# MCU.net
KiCad netlist of a schematic drawn in Altium Designer
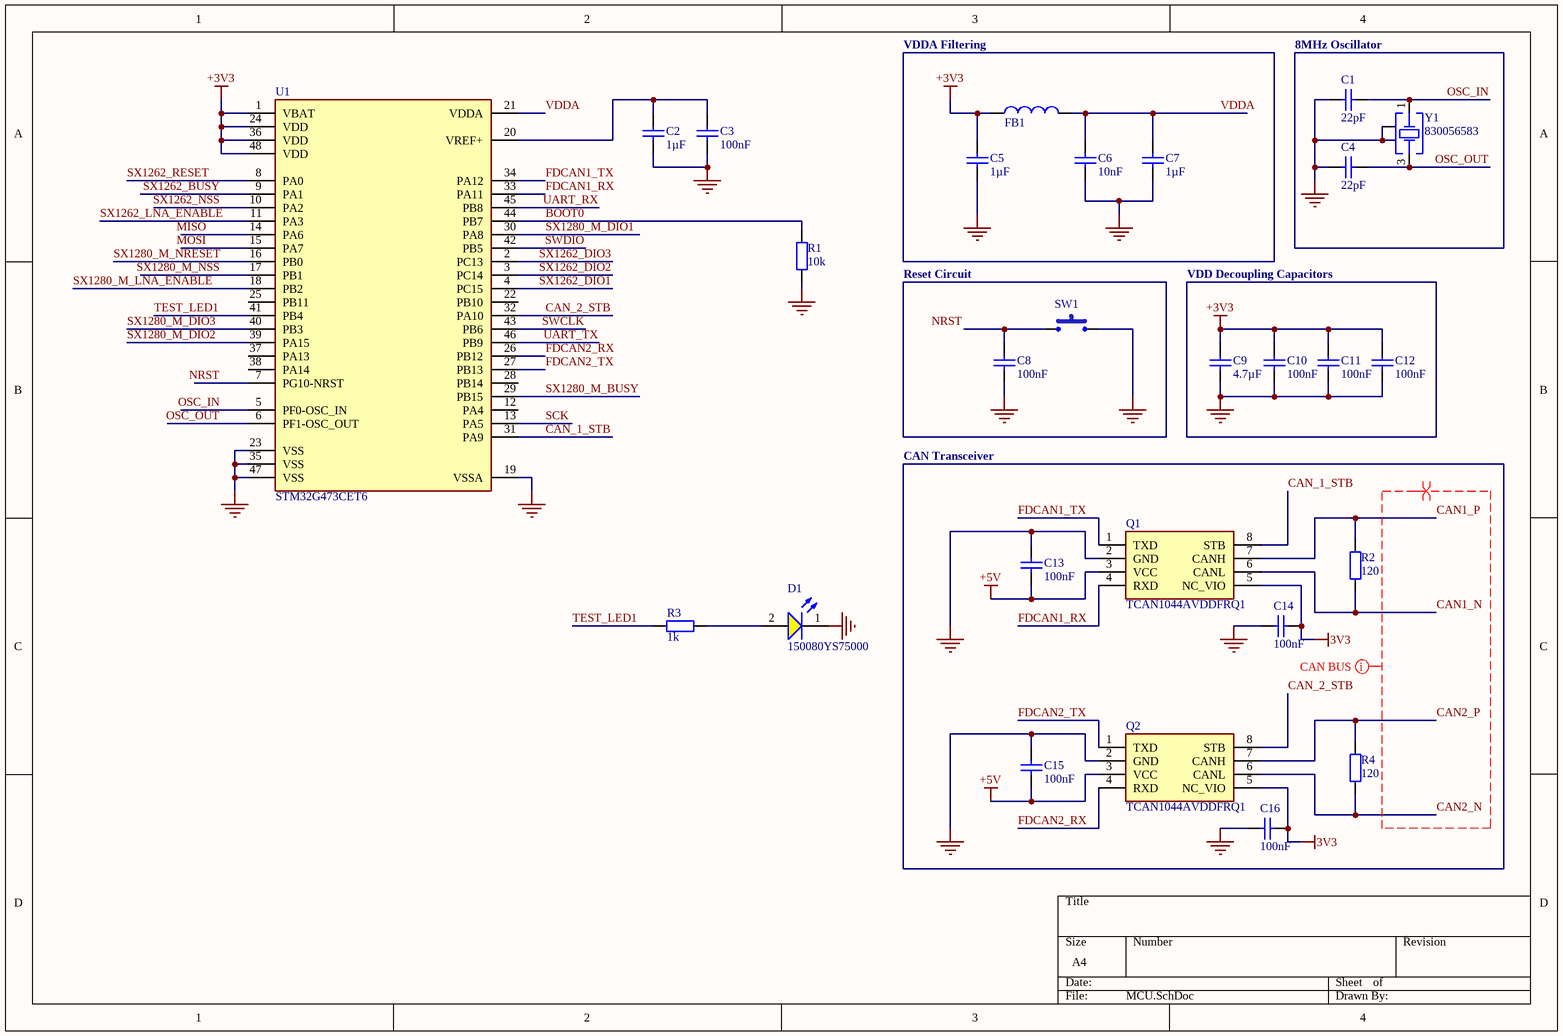
[diagram p0: MCU.SchDoc]

(export (version "E")
  (design (tool "Eeschema 10.0.6"))
  (components
    (comp (ref "C1")
      (value "22pF")
      (footprint "WCAP-CSGP_0603_L1.6W0.8H0.8_Reflow")
      (description "WCAP-CSGP Multilayer Ceramic Chip Capacitor, General Purpose, size 0603, NP0, 22pF, 25VDC")
      (fields
        (field (name "MANUFACTURER") "Wurth Elektronik")
        (field (name "MANUFACTURER PART NUMBER") "885012006034")
      )
      (libsource (lib "LEEM UPM") (part "885012209047R"))
    )
    (comp (ref "C2")
      (value "1µF")
      (footprint "WCAP-CSGP_0603_L1.6W0.8H0.8_Reflow")
      (description "WCAP-CSGP Multilayer Ceramic Chip Capacitor, General Purpose, size 0603, X7R, 1uF, 16VDC")
      (fields
        (field (name "MANUFACTURER") "Wurth Elektronik")
        (field (name "MANUFACTURER PART NUMBER") "885012206052")
      )
      (libsource (lib "LEEM UPM") (part "885012209047R"))
    )
    (comp (ref "C3")
      (value "100nF")
      (footprint "WCAP-CSGP_0603_L1.6W0.8H0.8_Reflow")
      (description "WCAP-CSGP Multilayer Ceramic Chip Capacitor, General Purpose, size 0603, X7R, 100nF, 25VDC")
      (fields
        (field (name "MANUFACTURER") "Wurth Elektronik")
        (field (name "MANUFACTURER PART NUMBER") "885012206071")
      )
      (libsource (lib "LEEM UPM") (part "885012209047R"))
    )
    (comp (ref "C4")
      (value "22pF")
      (footprint "WCAP-CSGP_0603_L1.6W0.8H0.8_Reflow")
      (description "WCAP-CSGP Multilayer Ceramic Chip Capacitor, General Purpose, size 0603, NP0, 22pF, 25VDC")
      (fields
        (field (name "MANUFACTURER") "Wurth Elektronik")
        (field (name "MANUFACTURER PART NUMBER") "885012006034")
      )
      (libsource (lib "LEEM UPM") (part "885012209047R"))
    )
    (comp (ref "C5")
      (value "1µF")
      (footprint "WCAP-CSGP_0603_L1.6W0.8H0.8_Reflow")
      (description "WCAP-CSGP Multilayer Ceramic Chip Capacitor, General Purpose, size 0603, X7R, 1uF, 16VDC")
      (fields
        (field (name "MANUFACTURER") "Wurth Elektronik")
        (field (name "MANUFACTURER PART NUMBER") "885012206052")
      )
      (libsource (lib "LEEM UPM") (part "885012209047R"))
    )
    (comp (ref "C6")
      (value "10nF")
      (footprint "WCAP-CSGP_0603_L1.6W0.8H0.8_Reflow")
      (description "WCAP-CSGP Multilayer Ceramic Chip Capacitor, General Purpose, size 0603, X7R, 10nF, 25VDC")
      (fields
        (field (name "MANUFACTURER") "Wurth Elektronik")
        (field (name "MANUFACTURER PART NUMBER") "885012206065")
      )
      (libsource (lib "LEEM UPM") (part "885012209047R"))
    )
    (comp (ref "C7")
      (value "1µF")
      (footprint "WCAP-CSGP_0603_L1.6W0.8H0.8_Reflow")
      (description "WCAP-CSGP Multilayer Ceramic Chip Capacitor, General Purpose, size 0603, X7R, 1uF, 16VDC")
      (fields
        (field (name "MANUFACTURER") "Wurth Elektronik")
        (field (name "MANUFACTURER PART NUMBER") "885012206052")
      )
      (libsource (lib "LEEM UPM") (part "885012209047R"))
    )
    (comp (ref "C8")
      (value "100nF")
      (footprint "WCAP-CSGP_0603_L1.6W0.8H0.8_Reflow")
      (description "WCAP-CSGP Multilayer Ceramic Chip Capacitor, General Purpose, size 0603, X7R, 100nF, 25VDC")
      (fields
        (field (name "MANUFACTURER") "Wurth Elektronik")
        (field (name "MANUFACTURER PART NUMBER") "885012206071")
      )
      (libsource (lib "LEEM UPM") (part "885012209047R"))
    )
    (comp (ref "C9")
      (value "4.7µF")
      (footprint "WCAP-CSGP_0603_L1.6W0.8H0.8_Reflow")
      (description "WCAP-CSGP Multilayer Ceramic Chip Capacitor, General Purpose, size 0603, X5R, 4.7uF, 10VDC")
      (fields
        (field (name "MANUFACTURER PART NUMBER") "885012106012")
        (field (name "MANUFACTURER") "Wurth Elektronik")
      )
      (libsource (lib "LEEM UPM") (part "885012209047R"))
    )
    (comp (ref "C10")
      (value "100nF")
      (footprint "WCAP-CSGP_0603_L1.6W0.8H0.8_Reflow")
      (description "WCAP-CSGP Multilayer Ceramic Chip Capacitor, General Purpose, size 0603, X7R, 100nF, 25VDC")
      (fields
        (field (name "MANUFACTURER") "Wurth Elektronik")
        (field (name "MANUFACTURER PART NUMBER") "885012206071")
      )
      (libsource (lib "LEEM UPM") (part "885012209047R"))
    )
    (comp (ref "C11")
      (value "100nF")
      (footprint "WCAP-CSGP_0603_L1.6W0.8H0.8_Reflow")
      (description "WCAP-CSGP Multilayer Ceramic Chip Capacitor, General Purpose, size 0603, X7R, 100nF, 25VDC")
      (fields
        (field (name "MANUFACTURER") "Wurth Elektronik")
        (field (name "MANUFACTURER PART NUMBER") "885012206071")
      )
      (libsource (lib "LEEM UPM") (part "885012209047R"))
    )
    (comp (ref "C12")
      (value "100nF")
      (footprint "WCAP-CSGP_0603_L1.6W0.8H0.8_Reflow")
      (description "WCAP-CSGP Multilayer Ceramic Chip Capacitor, General Purpose, size 0603, X7R, 100nF, 25VDC")
      (fields
        (field (name "MANUFACTURER") "Wurth Elektronik")
        (field (name "MANUFACTURER PART NUMBER") "885012206071")
      )
      (libsource (lib "LEEM UPM") (part "885012209047R"))
    )
    (comp (ref "C13")
      (value "100nF")
      (footprint "WCAP-CSGP_0603_L1.6W0.8H0.8_Reflow")
      (description "WCAP-CSGP Multilayer Ceramic Chip Capacitor, General Purpose, size 0603, X7R, 100nF, 25VDC")
      (fields
        (field (name "MANUFACTURER") "Wurth Elektronik")
        (field (name "MANUFACTURER PART NUMBER") "885012206071")
      )
      (libsource (lib "LEEM UPM") (part "885012209047R"))
    )
    (comp (ref "C14")
      (value "100nF")
      (footprint "WCAP-CSGP_0603_L1.6W0.8H0.8_Reflow")
      (description "WCAP-CSGP Multilayer Ceramic Chip Capacitor, General Purpose, size 0603, X7R, 100nF, 25VDC")
      (fields
        (field (name "MANUFACTURER") "Wurth Elektronik")
        (field (name "MANUFACTURER PART NUMBER") "885012206071")
      )
      (libsource (lib "LEEM UPM") (part "885012209047R"))
    )
    (comp (ref "C15")
      (value "100nF")
      (footprint "WCAP-CSGP_0603_L1.6W0.8H0.8_Reflow")
      (description "WCAP-CSGP Multilayer Ceramic Chip Capacitor, General Purpose, size 0603, X7R, 100nF, 25VDC")
      (fields
        (field (name "MANUFACTURER") "Wurth Elektronik")
        (field (name "MANUFACTURER PART NUMBER") "885012206071")
      )
      (libsource (lib "LEEM UPM") (part "885012209047R"))
    )
    (comp (ref "C16")
      (value "100nF")
      (footprint "WCAP-CSGP_0603_L1.6W0.8H0.8_Reflow")
      (description "WCAP-CSGP Multilayer Ceramic Chip Capacitor, General Purpose, size 0603, X7R, 100nF, 25VDC")
      (fields
        (field (name "MANUFACTURER") "Wurth Elektronik")
        (field (name "MANUFACTURER PART NUMBER") "885012206071")
      )
      (libsource (lib "LEEM UPM") (part "885012209047R"))
    )
    (comp (ref "D1")
      (value "150080YS75000")
      (footprint "WL-SMCW_0805_150080xx75000")
      (description "WL-SMCW Mono-color Chip LED Waterclear, SMT, size 0805, Yellow, 2V, 140°")
      (fields (field (name "MANUFACTURER") "Wurth Elektronik"))
      (libsource (lib "LEEM UPM") (part "150120YS87000"))
    )
    (comp (ref "FB1")
      (value "742792625")
      (footprint "WE-CBF_0603_L1.6W0.8H0.8_HC")
      (description "WE-CBF SMT EMI Suppression Ferrite Bead, size 0603, 120Ohm, 2A")
      (fields (field (name "MANUFACTURER") "Wurth Elektronik"))
      (libsource (lib "LEEM UPM") (part "7427928801"))
    )
    (comp (ref "Q1")
      (value "TCAN1044AVDDFRQ1")
      (footprint "FP-DDF0008A-MFG")
      (description "Enhanced automotive CAN transceiver with standby 8-SOT-23-THIN -40 to 150")
      (libsource (lib "LEEM UPM") (part "TCAN1044A"))
    )
    (comp (ref "Q2")
      (value "TCAN1044AVDDFRQ1")
      (footprint "FP-DDF0008A-MFG")
      (description "Enhanced automotive CAN transceiver with standby 8-SOT-23-THIN -40 to 150")
      (libsource (lib "LEEM UPM") (part "TCAN1044A"))
    )
    (comp (ref "R1")
      (value "10k")
      (footprint "WRIS-RSKS_0603_Reflow")
      (description "WRIS-RSKS Thick Film Resistor, size 0603, 10000Ohm, 100mW")
      (fields
        (field (name "MANUFACTURER") "Wurth Elektronik")
        (field (name "MANUFACTURER PART NUMBER") "560112116005")
      )
      (libsource (lib "") (part "560112140010_1"))
    )
    (comp (ref "R2")
      (value "120")
      (footprint "RCS0805120RFKEA-Footprint-1")
      (fields (field (name "POWER") "500mW") (field (name "Comment") "RCS0805120RFKEA"))
      (libsource (lib "LEEM UPM") (part "RCS0805120"))
    )
    (comp (ref "R3")
      (value "1k")
      (footprint "WRIS-RSKS_0603_Reflow")
      (description "WRIS-RSKS Thick Film Resistor, size 0603, 1000Ohm, 100mW")
      (fields
        (field (name "MANUFACTURER PART NUMBER") "560112116014")
        (field (name "MANUFACTURER") "Wurth Elektronik")
      )
      (libsource (lib "LEEM UPM") (part "560112140010"))
    )
    (comp (ref "R4")
      (value "120")
      (footprint "RCS0805120RFKEA-Footprint-1")
      (fields (field (name "POWER") "500mW") (field (name "Comment") "RCS0805120RFKEA"))
      (libsource (lib "LEEM UPM") (part "RCS0805120"))
    )
    (comp (ref "SW1")
      (value "PTS815SJM250SMTRLFS")
      (footprint "PTS815SJM250SMTRLFS-Footprint-1")
      (libsource (lib "LEEM UPM") (part "PTS815S"))
    )
    (comp (ref "U1")
      (value "STM32G473CET6")
      (footprint "STM32G0C1RET6-Footprint-1")
      (libsource (lib "LEEM UPM") (part "STM32G473xE"))
    )
    (comp (ref "Y1")
      (value "830056583")
      (footprint "WE-XTAL_CFPX-104")
      (description "WE-XTAL Quartz Crystal, SMT, CFPX-104, 10MHz, +/-30ppm")
      (fields (field (name "MANUFACTURER") "Wurth Elektronik"))
      (libsource (lib "LEEM UPM") (part "830108161901"))
    )
  )
  (nets
    (net (code "1") (name "+3V3") (class "Default")
      (node (ref "C10") (pin "2") (pinfunction "2_2") (pintype "passive"))
      (node (ref "C11") (pin "2") (pinfunction "2_2") (pintype "passive"))
      (node (ref "C12") (pin "2") (pinfunction "2_2") (pintype "passive"))
      (node (ref "C14") (pin "1") (pinfunction "1_1") (pintype "passive"))
      (node (ref "C16") (pin "1") (pinfunction "1_1") (pintype "passive"))
      (node (ref "C5") (pin "2") (pinfunction "2_2") (pintype "passive"))
      (node (ref "C9") (pin "2") (pinfunction "2_2") (pintype "passive"))
      (node (ref "FB1") (pin "1") (pinfunction "1_1") (pintype "passive"))
      (node (ref "Q1") (pin "5") (pinfunction "NC_VIO_5") (pintype "passive"))
      (node (ref "Q2") (pin "5") (pinfunction "NC_VIO_5") (pintype "passive"))
      (node (ref "U1") (pin "1") (pinfunction "VBAT_1") (pintype "passive"))
      (node (ref "U1") (pin "24") (pinfunction "VDD_24") (pintype "passive"))
      (node (ref "U1") (pin "36") (pinfunction "VDD_36") (pintype "passive"))
      (node (ref "U1") (pin "48") (pinfunction "VDD_48") (pintype "passive"))
    )
    (net (code "2") (name "+5V") (class "Default")
      (node (ref "C13") (pin "1") (pinfunction "1_1") (pintype "passive"))
      (node (ref "C15") (pin "1") (pinfunction "1_1") (pintype "passive"))
      (node (ref "Q1") (pin "3") (pinfunction "VCC_3") (pintype "passive"))
      (node (ref "Q2") (pin "3") (pinfunction "VCC_3") (pintype "passive"))
    )
    (net (code "3") (name "/BOOT0") (class "Default")
      (node (ref "R1") (pin "2") (pinfunction "2_2") (pintype "passive"))
      (node (ref "U1") (pin "44") (pinfunction "PB7_44") (pintype "passive"))
    )
    (net (code "4") (name "/CAN1_N") (class "Default")
      (node (ref "Q1") (pin "6") (pinfunction "CANL_6") (pintype "passive"))
      (node (ref "R2") (pin "1") (pinfunction "1_1") (pintype "passive"))
    )
    (net (code "5") (name "/CAN1_P") (class "Default")
      (node (ref "Q1") (pin "7") (pinfunction "CANH_7") (pintype "passive"))
      (node (ref "R2") (pin "2") (pinfunction "2_2") (pintype "passive"))
    )
    (net (code "6") (name "/CAN2_N") (class "Default")
      (node (ref "Q2") (pin "6") (pinfunction "CANL_6") (pintype "passive"))
      (node (ref "R4") (pin "1") (pinfunction "1_1") (pintype "passive"))
    )
    (net (code "7") (name "/CAN2_P") (class "Default")
      (node (ref "Q2") (pin "7") (pinfunction "CANH_7") (pintype "passive"))
      (node (ref "R4") (pin "2") (pinfunction "2_2") (pintype "passive"))
    )
    (net (code "8") (name "/CAN_1_STB") (class "Default")
      (node (ref "Q1") (pin "8") (pinfunction "STB_8") (pintype "passive"))
      (node (ref "U1") (pin "31") (pinfunction "PA9_31") (pintype "passive"))
    )
    (net (code "9") (name "/CAN_2_STB") (class "Default")
      (node (ref "Q2") (pin "8") (pinfunction "STB_8") (pintype "passive"))
      (node (ref "U1") (pin "32") (pinfunction "PA10_32") (pintype "passive"))
    )
    (net (code "10") (name "/FDCAN1_RX") (class "Default")
      (node (ref "Q1") (pin "4") (pinfunction "RXD_4") (pintype "passive"))
      (node (ref "U1") (pin "33") (pinfunction "PA11_33") (pintype "passive"))
    )
    (net (code "11") (name "/FDCAN1_TX") (class "Default")
      (node (ref "Q1") (pin "1") (pinfunction "TXD_1") (pintype "passive"))
      (node (ref "U1") (pin "34") (pinfunction "PA12_34") (pintype "passive"))
    )
    (net (code "12") (name "/FDCAN2_RX") (class "Default")
      (node (ref "Q2") (pin "4") (pinfunction "RXD_4") (pintype "passive"))
      (node (ref "U1") (pin "26") (pinfunction "PB12_26") (pintype "passive"))
    )
    (net (code "13") (name "/FDCAN2_TX") (class "Default")
      (node (ref "Q2") (pin "1") (pinfunction "TXD_1") (pintype "passive"))
      (node (ref "U1") (pin "27") (pinfunction "PB13_27") (pintype "passive"))
    )
    (net (code "14") (name "/MISO") (class "Default")
      (node (ref "U1") (pin "14") (pinfunction "PA6_14") (pintype "passive"))
    )
    (net (code "15") (name "/MOSI") (class "Default")
      (node (ref "U1") (pin "15") (pinfunction "PA7_15") (pintype "passive"))
    )
    (net (code "16") (name "/NRST") (class "Default")
      (node (ref "C8") (pin "2") (pinfunction "2_2") (pintype "passive"))
      (node (ref "SW1") (pin "1") (pinfunction "1_1") (pintype "passive"))
      (node (ref "U1") (pin "7") (pinfunction "PG10-NRST_7") (pintype "passive"))
    )
    (net (code "17") (name "/OSC_IN") (class "Default")
      (node (ref "C1") (pin "1") (pinfunction "1_1") (pintype "passive"))
      (node (ref "U1") (pin "5") (pinfunction "PF0-OSC_IN_5") (pintype "passive"))
      (node (ref "Y1") (pin "1") (pinfunction "Crystal_1") (pintype "passive"))
    )
    (net (code "18") (name "/OSC_OUT") (class "Default")
      (node (ref "C4") (pin "1") (pinfunction "1_1") (pintype "passive"))
      (node (ref "U1") (pin "6") (pinfunction "PF1-OSC_OUT_6") (pintype "passive"))
      (node (ref "Y1") (pin "3") (pinfunction "Crystal_3") (pintype "passive"))
    )
    (net (code "19") (name "/SCK") (class "Default")
      (node (ref "U1") (pin "13") (pinfunction "PA5_13") (pintype "passive"))
    )
    (net (code "20") (name "/SWCLK") (class "Default")
      (node (ref "U1") (pin "43") (pinfunction "PB6_43") (pintype "passive"))
    )
    (net (code "21") (name "/SWDIO") (class "Default")
      (node (ref "U1") (pin "42") (pinfunction "PB5_42") (pintype "passive"))
    )
    (net (code "22") (name "/SX1262_BUSY") (class "Default")
      (node (ref "U1") (pin "9") (pinfunction "PA1_9") (pintype "passive"))
    )
    (net (code "23") (name "/SX1262_DIO1") (class "Default")
      (node (ref "U1") (pin "4") (pinfunction "PC15_4") (pintype "passive"))
    )
    (net (code "24") (name "/SX1262_DIO2") (class "Default")
      (node (ref "U1") (pin "3") (pinfunction "PC14_3") (pintype "passive"))
    )
    (net (code "25") (name "/SX1262_DIO3") (class "Default")
      (node (ref "U1") (pin "2") (pinfunction "PC13_2") (pintype "passive"))
    )
    (net (code "26") (name "/SX1262_LNA_ENABLE") (class "Default")
      (node (ref "U1") (pin "11") (pinfunction "PA3_11") (pintype "passive"))
    )
    (net (code "27") (name "/SX1262_NSS") (class "Default")
      (node (ref "U1") (pin "10") (pinfunction "PA2_10") (pintype "passive"))
    )
    (net (code "28") (name "/SX1262_RESET") (class "Default")
      (node (ref "U1") (pin "8") (pinfunction "PA0_8") (pintype "passive"))
    )
    (net (code "29") (name "/SX1280_M_BUSY") (class "Default")
      (node (ref "U1") (pin "29") (pinfunction "PB15_29") (pintype "passive"))
    )
    (net (code "30") (name "/SX1280_M_DIO1") (class "Default")
      (node (ref "U1") (pin "30") (pinfunction "PA8_30") (pintype "passive"))
    )
    (net (code "31") (name "/SX1280_M_DIO2") (class "Default")
      (node (ref "U1") (pin "39") (pinfunction "PA15_39") (pintype "passive"))
    )
    (net (code "32") (name "/SX1280_M_DIO3") (class "Default")
      (node (ref "U1") (pin "40") (pinfunction "PB3_40") (pintype "passive"))
    )
    (net (code "33") (name "/SX1280_M_LNA_ENABLE") (class "Default")
      (node (ref "U1") (pin "18") (pinfunction "PB2_18") (pintype "passive"))
    )
    (net (code "34") (name "/SX1280_M_NRESET") (class "Default")
      (node (ref "U1") (pin "16") (pinfunction "PB0_16") (pintype "passive"))
    )
    (net (code "35") (name "/SX1280_M_NSS") (class "Default")
      (node (ref "U1") (pin "17") (pinfunction "PB1_17") (pintype "passive"))
    )
    (net (code "36") (name "/TEST_LED1") (class "Default")
      (node (ref "R3") (pin "2") (pinfunction "2_2") (pintype "passive"))
      (node (ref "U1") (pin "41") (pinfunction "PB4_41") (pintype "passive"))
    )
    (net (code "37") (name "/UART_RX") (class "Default")
      (node (ref "U1") (pin "45") (pinfunction "PB8_45") (pintype "passive"))
    )
    (net (code "38") (name "/UART_TX") (class "Default")
      (node (ref "U1") (pin "46") (pinfunction "PB9_46") (pintype "passive"))
    )
    (net (code "39") (name "/VDDA") (class "Default")
      (node (ref "C6") (pin "2") (pinfunction "2_2") (pintype "passive"))
      (node (ref "C7") (pin "2") (pinfunction "2_2") (pintype "passive"))
      (node (ref "FB1") (pin "2") (pinfunction "2_2") (pintype "passive"))
      (node (ref "U1") (pin "21") (pinfunction "VDDA_21") (pintype "passive"))
    )
    (net (code "40") (name "GND") (class "Default")
      (node (ref "C1") (pin "2") (pinfunction "2_2") (pintype "passive"))
      (node (ref "C10") (pin "1") (pinfunction "1_1") (pintype "passive"))
      (node (ref "C11") (pin "1") (pinfunction "1_1") (pintype "passive"))
      (node (ref "C12") (pin "1") (pinfunction "1_1") (pintype "passive"))
      (node (ref "C13") (pin "2") (pinfunction "2_2") (pintype "passive"))
      (node (ref "C14") (pin "2") (pinfunction "2_2") (pintype "passive"))
      (node (ref "C15") (pin "2") (pinfunction "2_2") (pintype "passive"))
      (node (ref "C16") (pin "2") (pinfunction "2_2") (pintype "passive"))
      (node (ref "C2") (pin "1") (pinfunction "1_1") (pintype "passive"))
      (node (ref "C3") (pin "1") (pinfunction "1_1") (pintype "passive"))
      (node (ref "C4") (pin "2") (pinfunction "2_2") (pintype "passive"))
      (node (ref "C5") (pin "1") (pinfunction "1_1") (pintype "passive"))
      (node (ref "C6") (pin "1") (pinfunction "1_1") (pintype "passive"))
      (node (ref "C7") (pin "1") (pinfunction "1_1") (pintype "passive"))
      (node (ref "C8") (pin "1") (pinfunction "1_1") (pintype "passive"))
      (node (ref "C9") (pin "1") (pinfunction "1_1") (pintype "passive"))
      (node (ref "D1") (pin "1") (pinfunction "K_1") (pintype "passive"))
      (node (ref "Q1") (pin "2") (pinfunction "GND_2") (pintype "passive"))
      (node (ref "Q2") (pin "2") (pinfunction "GND_2") (pintype "passive"))
      (node (ref "R1") (pin "1") (pinfunction "1_1") (pintype "passive"))
      (node (ref "SW1") (pin "2") (pinfunction "2_2") (pintype "passive"))
      (node (ref "U1") (pin "19") (pinfunction "VSSA_19") (pintype "passive"))
      (node (ref "U1") (pin "23") (pinfunction "VSS_23") (pintype "passive"))
      (node (ref "U1") (pin "35") (pinfunction "VSS_35") (pintype "passive"))
      (node (ref "U1") (pin "47") (pinfunction "VSS_47") (pintype "passive"))
      (node (ref "Y1") (pin "2") (pinfunction "GND_&_Lid_2") (pintype "passive"))
      (node (ref "Y1") (pin "4") (pinfunction "GND_&_Lid_4") (pintype "passive"))
    )
    (net (code "41") (name "Net-(D1-A)") (class "Default")
      (node (ref "D1") (pin "2") (pinfunction "A_2") (pintype "passive"))
      (node (ref "R3") (pin "1") (pinfunction "1_1") (pintype "passive"))
    )
    (net (code "42") (name "Net-(U1-VREF+)") (class "Default")
      (node (ref "C2") (pin "2") (pinfunction "2_2") (pintype "passive"))
      (node (ref "C3") (pin "2") (pinfunction "2_2") (pintype "passive"))
      (node (ref "U1") (pin "20") (pinfunction "VREF+_20") (pintype "passive"))
    )
    (net (code "43") (name "unconnected-(U1-PA4-Pad12)") (class "Default")
      (node (ref "U1") (pin "12") (pinfunction "PA4_12") (pintype "passive"))
    )
    (net (code "44") (name "unconnected-(U1-PA13-Pad37)") (class "Default")
      (node (ref "U1") (pin "37") (pinfunction "PA13_37") (pintype "passive"))
    )
    (net (code "45") (name "unconnected-(U1-PA14-Pad38)") (class "Default")
      (node (ref "U1") (pin "38") (pinfunction "PA14_38") (pintype "passive"))
    )
    (net (code "46") (name "unconnected-(U1-PB10-Pad22)") (class "Default")
      (node (ref "U1") (pin "22") (pinfunction "PB10_22") (pintype "passive"))
    )
    (net (code "47") (name "unconnected-(U1-PB11-Pad25)") (class "Default")
      (node (ref "U1") (pin "25") (pinfunction "PB11_25") (pintype "passive"))
    )
    (net (code "48") (name "unconnected-(U1-PB14-Pad28)") (class "Default")
      (node (ref "U1") (pin "28") (pinfunction "PB14_28") (pintype "passive"))
    )
  )
)
